# actuator_board.net
KiCad netlist of a schematic drawn in EAGLE
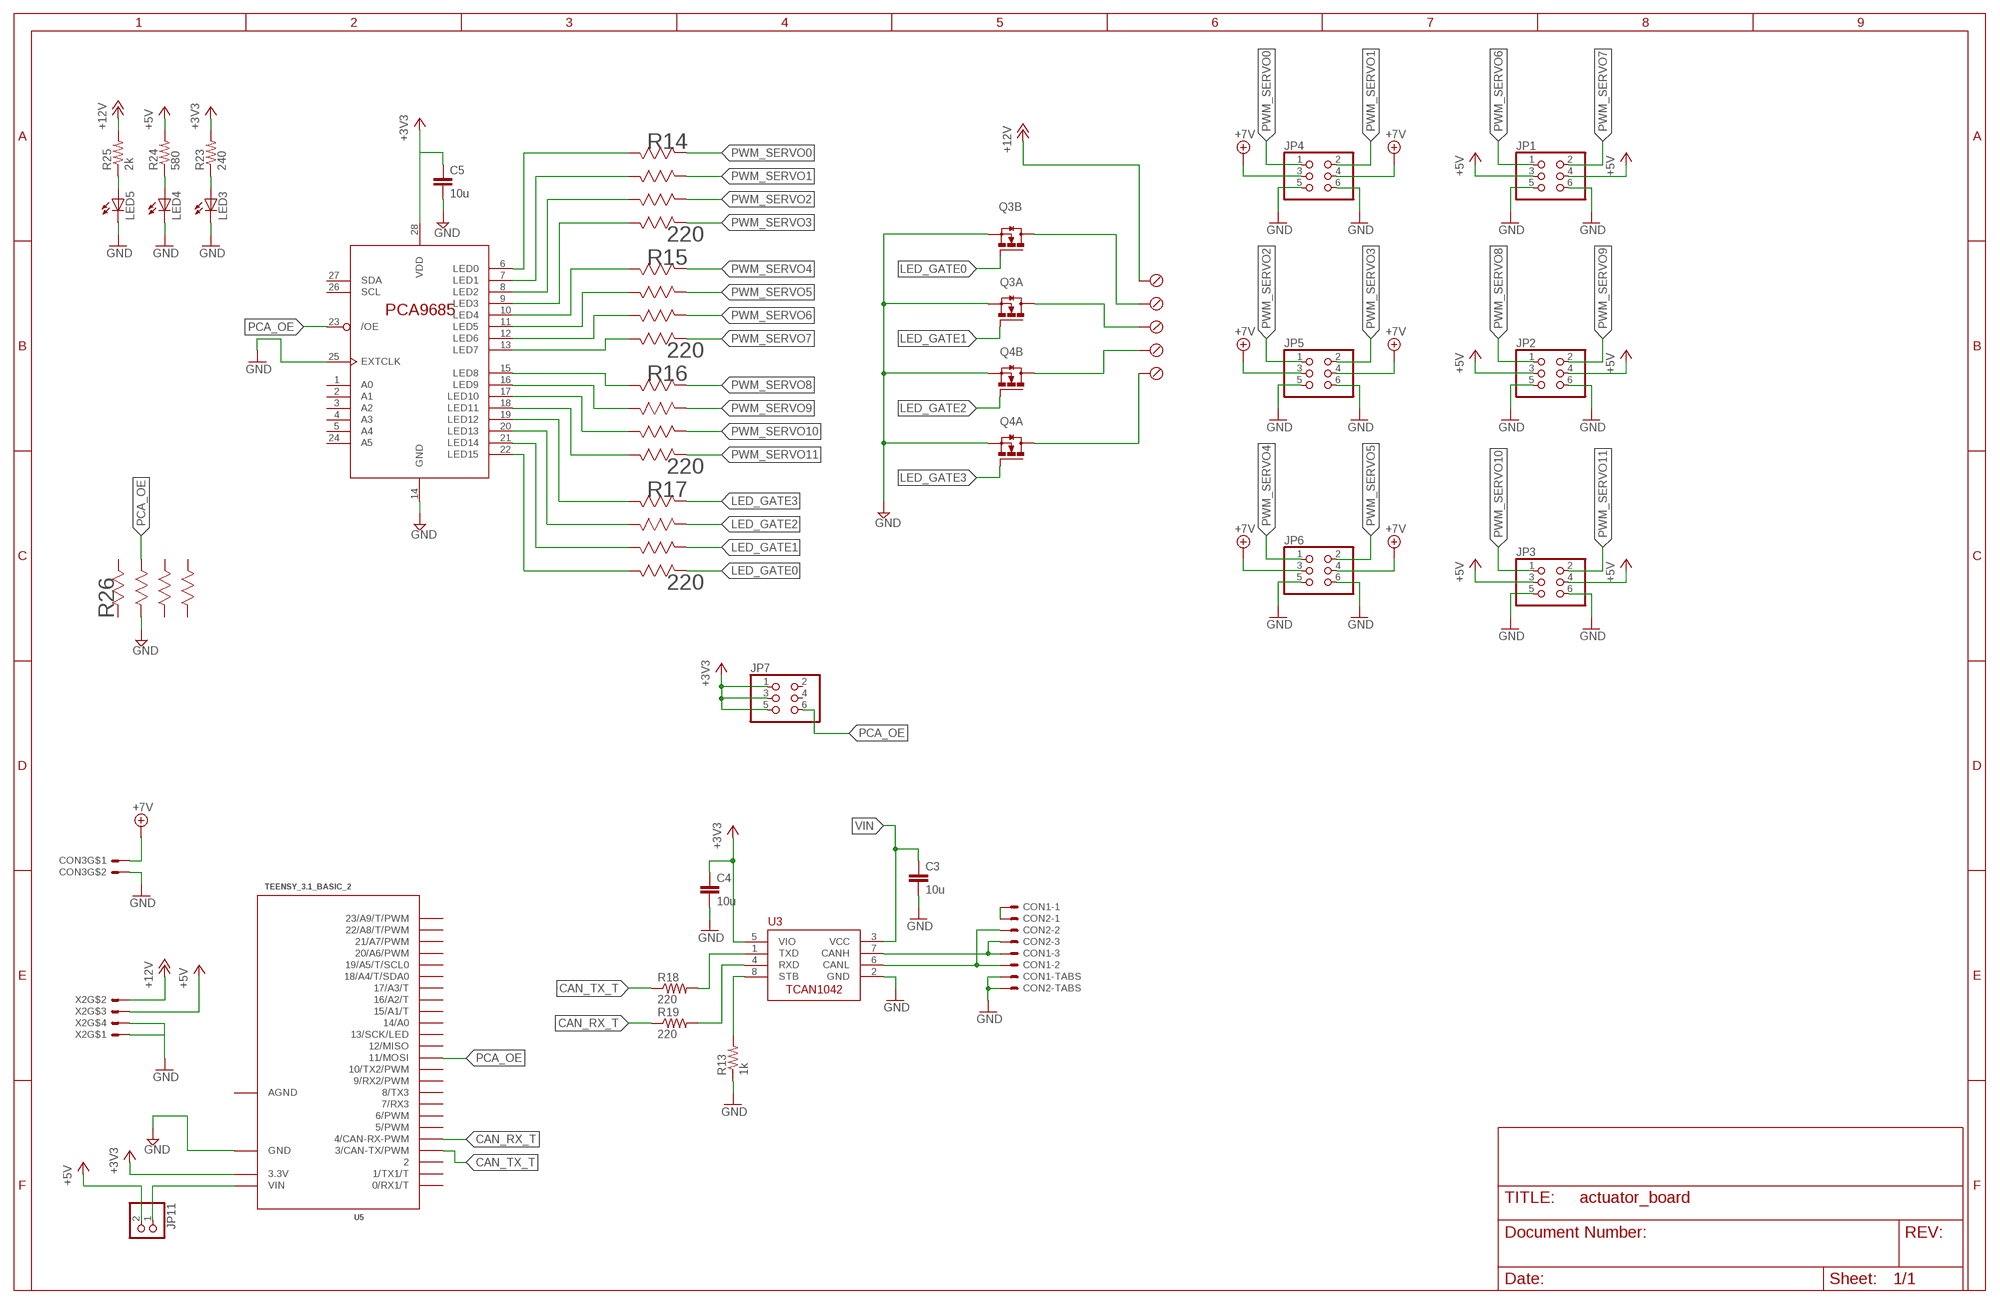
[diagram p0: schematic, sheet 1]

(export (version "E")
  (design (tool "Eeschema 10.0.6"))
  (components
    (comp (ref "C3")
      (value "10u")
      (footprint "eagle-import:C0805")
      (libsource (lib "eagle-import") (part "C-EUC0805"))
    )
    (comp (ref "C4")
      (value "10u")
      (footprint "eagle-import:C0805")
      (libsource (lib "eagle-import") (part "C-EUC0805"))
    )
    (comp (ref "C5")
      (value "10u")
      (footprint "eagle-import:C0805")
      (libsource (lib "eagle-import") (part "C-EUC0805"))
    )
    (comp (ref "CON1")
      (value "SM03B-GHS-TB")
      (footprint "eagle-import:SM03B-GHS-TB")
      (libsource (lib "eagle-import") (part "SM03B-GHS-TB"))
    )
    (comp (ref "CON2")
      (value "SM03B-GHS-TB")
      (footprint "eagle-import:SM03B-GHS-TB")
      (libsource (lib "eagle-import") (part "SM03B-GHS-TB"))
    )
    (comp (ref "CON3")
      (value "MOLEX_5566-2")
      (footprint "eagle-import:5566-2")
      (libsource (lib "eagle-import") (part "MOLEX_5566-2"))
    )
    (comp (ref "JP1")
      (value "PINHD-2X3")
      (footprint "eagle-import:2X03")
      (libsource (lib "eagle-import") (part "PINHD-2X3"))
    )
    (comp (ref "JP2")
      (value "PINHD-2X3")
      (footprint "eagle-import:2X03")
      (libsource (lib "eagle-import") (part "PINHD-2X3"))
    )
    (comp (ref "JP3")
      (value "PINHD-2X3")
      (footprint "eagle-import:2X03")
      (libsource (lib "eagle-import") (part "PINHD-2X3"))
    )
    (comp (ref "JP4")
      (value "PINHD-2X3")
      (footprint "eagle-import:2X03")
      (libsource (lib "eagle-import") (part "PINHD-2X3"))
    )
    (comp (ref "JP5")
      (value "PINHD-2X3")
      (footprint "eagle-import:2X03")
      (libsource (lib "eagle-import") (part "PINHD-2X3"))
    )
    (comp (ref "JP6")
      (value "PINHD-2X3")
      (footprint "eagle-import:2X03")
      (libsource (lib "eagle-import") (part "PINHD-2X3"))
    )
    (comp (ref "JP7")
      (value "PINHD-2X3")
      (footprint "eagle-import:2X03")
      (libsource (lib "eagle-import") (part "PINHD-2X3"))
    )
    (comp (ref "JP11")
      (value "PINHD-1X2")
      (footprint "eagle-import:1X02")
      (libsource (lib "eagle-import") (part "PINHD-1X2"))
    )
    (comp (ref "LED3")
      (value "LEDCHIPLED_1206")
      (footprint "eagle-import:CHIPLED_1206")
      (libsource (lib "eagle-import") (part "LEDCHIPLED_1206"))
    )
    (comp (ref "LED4")
      (value "LEDCHIPLED_1206")
      (footprint "eagle-import:CHIPLED_1206")
      (libsource (lib "eagle-import") (part "LEDCHIPLED_1206"))
    )
    (comp (ref "LED5")
      (value "LEDCHIPLED_1206")
      (footprint "eagle-import:CHIPLED_1206")
      (libsource (lib "eagle-import") (part "LEDCHIPLED_1206"))
    )
    (comp (ref "Q3")
      (value "IRL6372TRPBF")
      (footprint "eagle-import:SO-8")
      (libsource (lib "eagle-import") (part "IRL6372TRPBF"))
    )
    (comp (ref "Q4")
      (value "IRL6372TRPBF")
      (footprint "eagle-import:SO-8")
      (libsource (lib "eagle-import") (part "IRL6372TRPBF"))
    )
    (comp (ref "R13")
      (value "1k")
      (footprint "eagle-import:R0805")
      (libsource (lib "eagle-import") (part "R-US_R0805"))
    )
    (comp (ref "R14")
      (value "220")
      (footprint "eagle-import:EXBV8V-M")
      (fields (field (name "MANUFACTURER_PART_NUMBER") "EXBV8V221JV"))
      (libsource (lib "eagle-import") (part "EXB-V8V221JVEXBV8V-M"))
    )
    (comp (ref "R15")
      (value "220")
      (footprint "eagle-import:EXBV8V-M")
      (fields (field (name "MANUFACTURER_PART_NUMBER") "EXBV8V221JV"))
      (libsource (lib "eagle-import") (part "EXB-V8V221JVEXBV8V-M"))
    )
    (comp (ref "R16")
      (value "220")
      (footprint "eagle-import:EXBV8V-M")
      (fields (field (name "MANUFACTURER_PART_NUMBER") "EXBV8V221JV"))
      (libsource (lib "eagle-import") (part "EXB-V8V221JVEXBV8V-M"))
    )
    (comp (ref "R17")
      (value "220")
      (footprint "eagle-import:EXBV8V-M")
      (fields (field (name "MANUFACTURER_PART_NUMBER") "EXBV8V221JV"))
      (libsource (lib "eagle-import") (part "EXB-V8V221JVEXBV8V-M"))
    )
    (comp (ref "R18")
      (value "220")
      (footprint "eagle-import:R0805")
      (libsource (lib "eagle-import") (part "R-US_R0805"))
    )
    (comp (ref "R19")
      (value "220")
      (footprint "eagle-import:R0805")
      (libsource (lib "eagle-import") (part "R-US_R0805"))
    )
    (comp (ref "R23")
      (value "240")
      (footprint "eagle-import:R1206")
      (libsource (lib "eagle-import") (part "R-US_R1206"))
    )
    (comp (ref "R24")
      (value "580")
      (footprint "eagle-import:R1206")
      (libsource (lib "eagle-import") (part "R-US_R1206"))
    )
    (comp (ref "R25")
      (value "2k")
      (footprint "eagle-import:R1206")
      (libsource (lib "eagle-import") (part "R-US_R1206"))
    )
    (comp (ref "R26")
      (value "10k")
      (footprint "eagle-import:EXBV8V-M")
      (fields (field (name "MANUFACTURER_PART_NUMBER") "EXBV8V221JV"))
      (libsource (lib "eagle-import") (part "EXB-V8V221JVEXBV8V-M"))
    )
    (comp (ref "U$1")
      (value "SCREWLESS_TERMINAL_HEADERSCREWLESS_TERMINAL_HEADER")
      (footprint "eagle-import:1989777_TERMINALHEADER")
      (libsource (lib "eagle-import") (part "SCREWLESS_TERMINAL_HEADERSCREWLESS_TERMINAL_HEADER"))
    )
    (comp (ref "U3")
      (value "TCAN1042HVDR")
      (footprint "eagle-import:SO-8")
      (libsource (lib "eagle-import") (part "TCAN1042HVDR"))
    )
    (comp (ref "U4")
      (value "PCA9685PW")
      (footprint "eagle-import:TSSOP28")
      (libsource (lib "eagle-import") (part "PCA9685PW"))
    )
    (comp (ref "U5")
      (value "TEENSY_3.1_BASIC_2")
      (footprint "eagle-import:TEENSY_3.1_BASIC_2")
      (libsource (lib "eagle-import") (part "TEENSY_3.1_BASIC_2"))
    )
    (comp (ref "X2")
      (value "MOLEX_5566-4")
      (footprint "eagle-import:5566-4")
      (libsource (lib "eagle-import") (part "MOLEX_5566-4"))
    )
  )
  (nets
    (net (code "1") (name "+3V3") (class "Default")
      (node (ref "C4") (pin "1") (pinfunction "1_1") (pintype "passive"))
      (node (ref "C5") (pin "1") (pinfunction "1_1") (pintype "passive"))
      (node (ref "JP7") (pin "1") (pinfunction "1_1") (pintype "passive"))
      (node (ref "JP7") (pin "3") (pinfunction "3_3") (pintype "passive"))
      (node (ref "JP7") (pin "5") (pinfunction "5_5") (pintype "passive"))
      (node (ref "R23") (pin "2") (pinfunction "2_2") (pintype "passive"))
      (node (ref "U3") (pin "5") (pinfunction "VIO_5") (pintype "bidirectional"))
      (node (ref "U4") (pin "28") (pinfunction "VDD_28") (pintype "power_in"))
      (node (ref "U5") (pin "3.3V") (pinfunction "3.3V_3.3V") (pintype "power_in"))
    )
    (net (code "2") (name "+5V") (class "Default")
      (node (ref "JP1") (pin "3") (pinfunction "3_3") (pintype "passive"))
      (node (ref "JP1") (pin "4") (pinfunction "4_4") (pintype "passive"))
      (node (ref "JP11") (pin "2") (pinfunction "2_2") (pintype "passive"))
      (node (ref "JP2") (pin "3") (pinfunction "3_3") (pintype "passive"))
      (node (ref "JP2") (pin "4") (pinfunction "4_4") (pintype "passive"))
      (node (ref "JP3") (pin "3") (pinfunction "3_3") (pintype "passive"))
      (node (ref "JP3") (pin "4") (pinfunction "4_4") (pintype "passive"))
      (node (ref "R24") (pin "2") (pinfunction "2_2") (pintype "passive"))
      (node (ref "X2") (pin "3") (pinfunction "S_3") (pintype "passive"))
    )
    (net (code "3") (name "+7V") (class "Default")
      (node (ref "CON3") (pin "1") (pinfunction "S_1") (pintype "passive"))
      (node (ref "JP4") (pin "3") (pinfunction "3_3") (pintype "passive"))
      (node (ref "JP4") (pin "4") (pinfunction "4_4") (pintype "passive"))
      (node (ref "JP5") (pin "3") (pinfunction "3_3") (pintype "passive"))
      (node (ref "JP5") (pin "4") (pinfunction "4_4") (pintype "passive"))
      (node (ref "JP6") (pin "3") (pinfunction "3_3") (pintype "passive"))
      (node (ref "JP6") (pin "4") (pinfunction "4_4") (pintype "passive"))
    )
    (net (code "4") (name "+12V") (class "Default")
      (node (ref "R25") (pin "2") (pinfunction "2_2") (pintype "passive"))
      (node (ref "U$1") (pin "P$5") (pinfunction "12+_P$5") (pintype "passive"))
      (node (ref "X2") (pin "2") (pinfunction "S_2") (pintype "passive"))
    )
    (net (code "5") (name "/AGND") (class "Default")
      (node (ref "U5") (pin "AGND") (pinfunction "AGND_AGND") (pintype "power_in"))
    )
    (net (code "6") (name "CAN_RX_T") (class "Default")
      (node (ref "R19") (pin "1") (pinfunction "1_1") (pintype "passive"))
      (node (ref "U5") (pin "4") (pinfunction "4/CAN-RX-PWM_4") (pintype "bidirectional"))
    )
    (net (code "7") (name "CAN_TX_T") (class "Default")
      (node (ref "R18") (pin "1") (pinfunction "1_1") (pintype "passive"))
      (node (ref "U5") (pin "3") (pinfunction "3/CAN-TX/PWM_3") (pintype "bidirectional"))
    )
    (net (code "8") (name "GND") (class "Default")
      (node (ref "C3") (pin "2") (pinfunction "2_2") (pintype "passive"))
      (node (ref "C4") (pin "2") (pinfunction "2_2") (pintype "passive"))
      (node (ref "C5") (pin "2") (pinfunction "2_2") (pintype "passive"))
      (node (ref "CON1") (pin "P$4") (pinfunction "S_P$4") (pintype "passive"))
      (node (ref "CON1") (pin "P$5") (pinfunction "S_P$5") (pintype "passive"))
      (node (ref "CON2") (pin "P$4") (pinfunction "S_P$4") (pintype "passive"))
      (node (ref "CON2") (pin "P$5") (pinfunction "S_P$5") (pintype "passive"))
      (node (ref "CON3") (pin "2") (pinfunction "S_2") (pintype "passive"))
      (node (ref "JP1") (pin "5") (pinfunction "5_5") (pintype "passive"))
      (node (ref "JP1") (pin "6") (pinfunction "6_6") (pintype "passive"))
      (node (ref "JP2") (pin "5") (pinfunction "5_5") (pintype "passive"))
      (node (ref "JP2") (pin "6") (pinfunction "6_6") (pintype "passive"))
      (node (ref "JP3") (pin "5") (pinfunction "5_5") (pintype "passive"))
      (node (ref "JP3") (pin "6") (pinfunction "6_6") (pintype "passive"))
      (node (ref "JP4") (pin "5") (pinfunction "5_5") (pintype "passive"))
      (node (ref "JP4") (pin "6") (pinfunction "6_6") (pintype "passive"))
      (node (ref "JP5") (pin "5") (pinfunction "5_5") (pintype "passive"))
      (node (ref "JP5") (pin "6") (pinfunction "6_6") (pintype "passive"))
      (node (ref "JP6") (pin "5") (pinfunction "5_5") (pintype "passive"))
      (node (ref "JP6") (pin "6") (pinfunction "6_6") (pintype "passive"))
      (node (ref "LED3") (pin "C") (pinfunction "C_C") (pintype "passive"))
      (node (ref "LED4") (pin "C") (pinfunction "C_C") (pintype "passive"))
      (node (ref "LED5") (pin "C") (pinfunction "C_C") (pintype "passive"))
      (node (ref "Q3") (pin "1") (pinfunction "S_1") (pintype "passive"))
      (node (ref "Q3") (pin "3") (pinfunction "S_3") (pintype "passive"))
      (node (ref "Q4") (pin "1") (pinfunction "S_1") (pintype "passive"))
      (node (ref "Q4") (pin "3") (pinfunction "S_3") (pintype "passive"))
      (node (ref "R13") (pin "1") (pinfunction "1_1") (pintype "passive"))
      (node (ref "R26") (pin "2") (pinfunction "23_2") (pintype "passive"))
      (node (ref "U3") (pin "2") (pinfunction "GND_2") (pintype "bidirectional"))
      (node (ref "U4") (pin "14") (pinfunction "GND_14") (pintype "power_in"))
      (node (ref "U4") (pin "25") (pinfunction "EXTCLK_25") (pintype "input"))
      (node (ref "U5") (pin "GND") (pinfunction "GND_GND") (pintype "power_in"))
      (node (ref "X2") (pin "1") (pinfunction "S_1") (pintype "passive"))
      (node (ref "X2") (pin "4") (pinfunction "S_4") (pintype "passive"))
    )
    (net (code "9") (name "LED_GATE0") (class "Default")
      (node (ref "Q3") (pin "2") (pinfunction "G_2") (pintype "passive"))
      (node (ref "R17") (pin "4") (pinfunction "47_4") (pintype "passive"))
    )
    (net (code "10") (name "LED_GATE1") (class "Default")
      (node (ref "Q3") (pin "4") (pinfunction "G_4") (pintype "passive"))
      (node (ref "R17") (pin "3") (pinfunction "35_3") (pintype "passive"))
    )
    (net (code "11") (name "LED_GATE2") (class "Default")
      (node (ref "Q4") (pin "2") (pinfunction "G_2") (pintype "passive"))
      (node (ref "R17") (pin "2") (pinfunction "23_2") (pintype "passive"))
    )
    (net (code "12") (name "LED_GATE3") (class "Default")
      (node (ref "Q4") (pin "4") (pinfunction "G_4") (pintype "passive"))
      (node (ref "R17") (pin "1") (pinfunction "11_1") (pintype "passive"))
    )
    (net (code "13") (name "Net-(CON1A-S)") (class "Default")
      (node (ref "CON1") (pin "P$1") (pinfunction "S_P$1") (pintype "passive"))
      (node (ref "CON2") (pin "P$1") (pinfunction "S_P$1") (pintype "passive"))
    )
    (net (code "14") (name "Net-(CON1B-S)") (class "Default")
      (node (ref "CON1") (pin "P$2") (pinfunction "S_P$2") (pintype "passive"))
      (node (ref "CON2") (pin "P$2") (pinfunction "S_P$2") (pintype "passive"))
      (node (ref "U3") (pin "6") (pinfunction "CANL_6") (pintype "bidirectional"))
    )
    (net (code "15") (name "Net-(CON1C-S)") (class "Default")
      (node (ref "CON1") (pin "P$3") (pinfunction "S_P$3") (pintype "passive"))
      (node (ref "CON2") (pin "P$3") (pinfunction "S_P$3") (pintype "passive"))
      (node (ref "U3") (pin "7") (pinfunction "CANH_7") (pintype "bidirectional"))
    )
    (net (code "16") (name "Net-(LED3-PadA)") (class "Default")
      (node (ref "LED3") (pin "A") (pinfunction "A_A") (pintype "passive"))
      (node (ref "R23") (pin "1") (pinfunction "1_1") (pintype "passive"))
    )
    (net (code "17") (name "Net-(LED4-PadA)") (class "Default")
      (node (ref "LED4") (pin "A") (pinfunction "A_A") (pintype "passive"))
      (node (ref "R24") (pin "1") (pinfunction "1_1") (pintype "passive"))
    )
    (net (code "18") (name "Net-(LED5-PadA)") (class "Default")
      (node (ref "LED5") (pin "A") (pinfunction "A_A") (pintype "passive"))
      (node (ref "R25") (pin "1") (pinfunction "1_1") (pintype "passive"))
    )
    (net (code "19") (name "Net-(R14-58)") (class "Default")
      (node (ref "R14") (pin "5") (pinfunction "58_5") (pintype "passive"))
      (node (ref "U4") (pin "9") (pinfunction "LED3_9") (pintype "bidirectional"))
    )
    (net (code "20") (name "Net-(R14-66)") (class "Default")
      (node (ref "R14") (pin "6") (pinfunction "66_6") (pintype "passive"))
      (node (ref "U4") (pin "8") (pinfunction "LED2_8") (pintype "bidirectional"))
    )
    (net (code "21") (name "Net-(R14-74)") (class "Default")
      (node (ref "R14") (pin "7") (pinfunction "74_7") (pintype "passive"))
      (node (ref "U4") (pin "7") (pinfunction "LED1_7") (pintype "bidirectional"))
    )
    (net (code "22") (name "Net-(R14-82)") (class "Default")
      (node (ref "R14") (pin "8") (pinfunction "82_8") (pintype "passive"))
      (node (ref "U4") (pin "6") (pinfunction "LED0_6") (pintype "bidirectional"))
    )
    (net (code "23") (name "Net-(R15-58)") (class "Default")
      (node (ref "R15") (pin "5") (pinfunction "58_5") (pintype "passive"))
      (node (ref "U4") (pin "13") (pinfunction "LED7_13") (pintype "bidirectional"))
    )
    (net (code "24") (name "Net-(R15-66)") (class "Default")
      (node (ref "R15") (pin "6") (pinfunction "66_6") (pintype "passive"))
      (node (ref "U4") (pin "12") (pinfunction "LED6_12") (pintype "bidirectional"))
    )
    (net (code "25") (name "Net-(R15-74)") (class "Default")
      (node (ref "R15") (pin "7") (pinfunction "74_7") (pintype "passive"))
      (node (ref "U4") (pin "11") (pinfunction "LED5_11") (pintype "bidirectional"))
    )
    (net (code "26") (name "Net-(R15-82)") (class "Default")
      (node (ref "R15") (pin "8") (pinfunction "82_8") (pintype "passive"))
      (node (ref "U4") (pin "10") (pinfunction "LED4_10") (pintype "bidirectional"))
    )
    (net (code "27") (name "Net-(R16-58)") (class "Default")
      (node (ref "R16") (pin "5") (pinfunction "58_5") (pintype "passive"))
      (node (ref "U4") (pin "18") (pinfunction "LED11_18") (pintype "bidirectional"))
    )
    (net (code "28") (name "Net-(R16-66)") (class "Default")
      (node (ref "R16") (pin "6") (pinfunction "66_6") (pintype "passive"))
      (node (ref "U4") (pin "17") (pinfunction "LED10_17") (pintype "bidirectional"))
    )
    (net (code "29") (name "Net-(R16-74)") (class "Default")
      (node (ref "R16") (pin "7") (pinfunction "74_7") (pintype "passive"))
      (node (ref "U4") (pin "16") (pinfunction "LED9_16") (pintype "bidirectional"))
    )
    (net (code "30") (name "Net-(R16-82)") (class "Default")
      (node (ref "R16") (pin "8") (pinfunction "82_8") (pintype "passive"))
      (node (ref "U4") (pin "15") (pinfunction "LED8_15") (pintype "bidirectional"))
    )
    (net (code "31") (name "Net-(R17-58)") (class "Default")
      (node (ref "R17") (pin "5") (pinfunction "58_5") (pintype "passive"))
      (node (ref "U4") (pin "22") (pinfunction "LED15_22") (pintype "bidirectional"))
    )
    (net (code "32") (name "Net-(R17-66)") (class "Default")
      (node (ref "R17") (pin "6") (pinfunction "66_6") (pintype "passive"))
      (node (ref "U4") (pin "21") (pinfunction "LED14_21") (pintype "bidirectional"))
    )
    (net (code "33") (name "Net-(R17-74)") (class "Default")
      (node (ref "R17") (pin "7") (pinfunction "74_7") (pintype "passive"))
      (node (ref "U4") (pin "20") (pinfunction "LED13_20") (pintype "bidirectional"))
    )
    (net (code "34") (name "Net-(R17-82)") (class "Default")
      (node (ref "R17") (pin "8") (pinfunction "82_8") (pintype "passive"))
      (node (ref "U4") (pin "19") (pinfunction "LED12_19") (pintype "bidirectional"))
    )
    (net (code "35") (name "Net-(U$1-LED0)") (class "Default")
      (node (ref "Q3") (pin "7") (pinfunction "D_7") (pintype "passive"))
      (node (ref "Q3") (pin "8") (pinfunction "D_8") (pintype "passive"))
      (node (ref "U$1") (pin "P$4") (pinfunction "LED0_P$4") (pintype "passive"))
    )
    (net (code "36") (name "Net-(U$1-LED1)") (class "Default")
      (node (ref "Q3") (pin "5") (pinfunction "D_5") (pintype "passive"))
      (node (ref "Q3") (pin "6") (pinfunction "D_6") (pintype "passive"))
      (node (ref "U$1") (pin "P$3") (pinfunction "LED1_P$3") (pintype "passive"))
    )
    (net (code "37") (name "Net-(U$1-LED2)") (class "Default")
      (node (ref "Q4") (pin "7") (pinfunction "D_7") (pintype "passive"))
      (node (ref "Q4") (pin "8") (pinfunction "D_8") (pintype "passive"))
      (node (ref "U$1") (pin "P$2") (pinfunction "LED2_P$2") (pintype "passive"))
    )
    (net (code "38") (name "Net-(U$1-LED3)") (class "Default")
      (node (ref "Q4") (pin "5") (pinfunction "D_5") (pintype "passive"))
      (node (ref "Q4") (pin "6") (pinfunction "D_6") (pintype "passive"))
      (node (ref "U$1") (pin "P$1") (pinfunction "LED3_P$1") (pintype "passive"))
    )
    (net (code "39") (name "Net-(U3-RXD)") (class "Default")
      (node (ref "R19") (pin "2") (pinfunction "2_2") (pintype "passive"))
      (node (ref "U3") (pin "4") (pinfunction "RXD_4") (pintype "bidirectional"))
    )
    (net (code "40") (name "Net-(U3-STB)") (class "Default")
      (node (ref "R13") (pin "2") (pinfunction "2_2") (pintype "passive"))
      (node (ref "U3") (pin "8") (pinfunction "STB_8") (pintype "bidirectional"))
    )
    (net (code "41") (name "Net-(U3-TXD)") (class "Default")
      (node (ref "R18") (pin "2") (pinfunction "2_2") (pintype "passive"))
      (node (ref "U3") (pin "1") (pinfunction "TXD_1") (pintype "bidirectional"))
    )
    (net (code "42") (name "PCA_OE") (class "Default")
      (node (ref "JP7") (pin "6") (pinfunction "6_6") (pintype "passive"))
      (node (ref "R26") (pin "7") (pinfunction "74_7") (pintype "passive"))
      (node (ref "U4") (pin "23") (pinfunction "/OE_23") (pintype "bidirectional"))
      (node (ref "U5") (pin "11") (pinfunction "11/MOSI_11") (pintype "bidirectional"))
    )
    (net (code "43") (name "PWM_SERVO0") (class "Default")
      (node (ref "JP4") (pin "1") (pinfunction "1_1") (pintype "passive"))
      (node (ref "R14") (pin "1") (pinfunction "11_1") (pintype "passive"))
    )
    (net (code "44") (name "PWM_SERVO1") (class "Default")
      (node (ref "JP4") (pin "2") (pinfunction "2_2") (pintype "passive"))
      (node (ref "R14") (pin "2") (pinfunction "23_2") (pintype "passive"))
    )
    (net (code "45") (name "PWM_SERVO2") (class "Default")
      (node (ref "JP5") (pin "1") (pinfunction "1_1") (pintype "passive"))
      (node (ref "R14") (pin "3") (pinfunction "35_3") (pintype "passive"))
    )
    (net (code "46") (name "PWM_SERVO3") (class "Default")
      (node (ref "JP5") (pin "2") (pinfunction "2_2") (pintype "passive"))
      (node (ref "R14") (pin "4") (pinfunction "47_4") (pintype "passive"))
    )
    (net (code "47") (name "PWM_SERVO4") (class "Default")
      (node (ref "JP6") (pin "1") (pinfunction "1_1") (pintype "passive"))
      (node (ref "R15") (pin "1") (pinfunction "11_1") (pintype "passive"))
    )
    (net (code "48") (name "PWM_SERVO5") (class "Default")
      (node (ref "JP6") (pin "2") (pinfunction "2_2") (pintype "passive"))
      (node (ref "R15") (pin "2") (pinfunction "23_2") (pintype "passive"))
    )
    (net (code "49") (name "PWM_SERVO6") (class "Default")
      (node (ref "JP1") (pin "1") (pinfunction "1_1") (pintype "passive"))
      (node (ref "R15") (pin "3") (pinfunction "35_3") (pintype "passive"))
    )
    (net (code "50") (name "PWM_SERVO7") (class "Default")
      (node (ref "JP1") (pin "2") (pinfunction "2_2") (pintype "passive"))
      (node (ref "R15") (pin "4") (pinfunction "47_4") (pintype "passive"))
    )
    (net (code "51") (name "PWM_SERVO8") (class "Default")
      (node (ref "JP2") (pin "1") (pinfunction "1_1") (pintype "passive"))
      (node (ref "R16") (pin "1") (pinfunction "11_1") (pintype "passive"))
    )
    (net (code "52") (name "PWM_SERVO9") (class "Default")
      (node (ref "JP2") (pin "2") (pinfunction "2_2") (pintype "passive"))
      (node (ref "R16") (pin "2") (pinfunction "23_2") (pintype "passive"))
    )
    (net (code "53") (name "PWM_SERVO10") (class "Default")
      (node (ref "JP3") (pin "1") (pinfunction "1_1") (pintype "passive"))
      (node (ref "R16") (pin "3") (pinfunction "35_3") (pintype "passive"))
    )
    (net (code "54") (name "PWM_SERVO11") (class "Default")
      (node (ref "JP3") (pin "2") (pinfunction "2_2") (pintype "passive"))
      (node (ref "R16") (pin "4") (pinfunction "47_4") (pintype "passive"))
    )
    (net (code "55") (name "VIN") (class "Default")
      (node (ref "C3") (pin "1") (pinfunction "1_1") (pintype "passive"))
      (node (ref "JP11") (pin "1") (pinfunction "1_1") (pintype "passive"))
      (node (ref "U3") (pin "3") (pinfunction "VCC_3") (pintype "bidirectional"))
      (node (ref "U5") (pin "VIN") (pinfunction "VIN_VIN") (pintype "power_in"))
    )
    (net (code "56") (name "unconnected-(JP7-Pad2)") (class "Default")
      (node (ref "JP7") (pin "2") (pinfunction "2_2") (pintype "passive"))
    )
    (net (code "57") (name "unconnected-(JP7-Pad4)") (class "Default")
      (node (ref "JP7") (pin "4") (pinfunction "4_4") (pintype "passive"))
    )
    (net (code "58") (name "unconnected-(R26-11-Pad1)") (class "Default")
      (node (ref "R26") (pin "1") (pinfunction "11_1") (pintype "passive"))
    )
    (net (code "59") (name "unconnected-(R26-35-Pad3)") (class "Default")
      (node (ref "R26") (pin "3") (pinfunction "35_3") (pintype "passive"))
    )
    (net (code "60") (name "unconnected-(R26-47-Pad4)") (class "Default")
      (node (ref "R26") (pin "4") (pinfunction "47_4") (pintype "passive"))
    )
    (net (code "61") (name "unconnected-(R26-58-Pad5)") (class "Default")
      (node (ref "R26") (pin "5") (pinfunction "58_5") (pintype "passive"))
    )
    (net (code "62") (name "unconnected-(R26-66-Pad6)") (class "Default")
      (node (ref "R26") (pin "6") (pinfunction "66_6") (pintype "passive"))
    )
    (net (code "63") (name "unconnected-(R26-82-Pad8)") (class "Default")
      (node (ref "R26") (pin "8") (pinfunction "82_8") (pintype "passive"))
    )
    (net (code "64") (name "unconnected-(U4-A0-Pad1)") (class "Default")
      (node (ref "U4") (pin "1") (pinfunction "A0_1") (pintype "bidirectional"))
    )
    (net (code "65") (name "unconnected-(U4-A1-Pad2)") (class "Default")
      (node (ref "U4") (pin "2") (pinfunction "A1_2") (pintype "bidirectional"))
    )
    (net (code "66") (name "unconnected-(U4-A2-Pad3)") (class "Default")
      (node (ref "U4") (pin "3") (pinfunction "A2_3") (pintype "bidirectional"))
    )
    (net (code "67") (name "unconnected-(U4-A3-Pad4)") (class "Default")
      (node (ref "U4") (pin "4") (pinfunction "A3_4") (pintype "bidirectional"))
    )
    (net (code "68") (name "unconnected-(U4-A4-Pad5)") (class "Default")
      (node (ref "U4") (pin "5") (pinfunction "A4_5") (pintype "bidirectional"))
    )
    (net (code "69") (name "unconnected-(U4-A5-Pad24)") (class "Default")
      (node (ref "U4") (pin "24") (pinfunction "A5_24") (pintype "bidirectional"))
    )
    (net (code "70") (name "unconnected-(U4-SCL-Pad26)") (class "Default")
      (node (ref "U4") (pin "26") (pinfunction "SCL_26") (pintype "bidirectional"))
    )
    (net (code "71") (name "unconnected-(U4-SDA-Pad27)") (class "Default")
      (node (ref "U4") (pin "27") (pinfunction "SDA_27") (pintype "bidirectional"))
    )
    (net (code "72") (name "unconnected-(U5-0{slash}RX1{slash}T-Pad0)") (class "Default")
      (node (ref "U5") (pin "0") (pinfunction "0/RX1/T_0") (pintype "bidirectional"))
    )
    (net (code "73") (name "unconnected-(U5-1{slash}TX1{slash}T-Pad1)") (class "Default")
      (node (ref "U5") (pin "1") (pinfunction "1/TX1/T_1") (pintype "bidirectional"))
    )
    (net (code "74") (name "unconnected-(U5-5{slash}PWM-Pad5)") (class "Default")
      (node (ref "U5") (pin "5") (pinfunction "5/PWM_5") (pintype "bidirectional"))
    )
    (net (code "75") (name "unconnected-(U5-6{slash}PWM-Pad6)") (class "Default")
      (node (ref "U5") (pin "6") (pinfunction "6/PWM_6") (pintype "bidirectional"))
    )
    (net (code "76") (name "unconnected-(U5-7{slash}RX3-Pad7)") (class "Default")
      (node (ref "U5") (pin "7") (pinfunction "7/RX3_7") (pintype "bidirectional"))
    )
    (net (code "77") (name "unconnected-(U5-8{slash}TX3-Pad8)") (class "Default")
      (node (ref "U5") (pin "8") (pinfunction "8/TX3_8") (pintype "bidirectional"))
    )
    (net (code "78") (name "unconnected-(U5-9{slash}RX2{slash}PWM-Pad9)") (class "Default")
      (node (ref "U5") (pin "9") (pinfunction "9/RX2/PWM_9") (pintype "bidirectional"))
    )
    (net (code "79") (name "unconnected-(U5-10{slash}TX2{slash}PWM-Pad10)") (class "Default")
      (node (ref "U5") (pin "10") (pinfunction "10/TX2/PWM_10") (pintype "bidirectional"))
    )
    (net (code "80") (name "unconnected-(U5-12{slash}MISO-Pad12)") (class "Default")
      (node (ref "U5") (pin "12") (pinfunction "12/MISO_12") (pintype "bidirectional"))
    )
    (net (code "81") (name "unconnected-(U5-13{slash}SCK{slash}LED-Pad13)") (class "Default")
      (node (ref "U5") (pin "13") (pinfunction "13/SCK/LED_13") (pintype "bidirectional"))
    )
    (net (code "82") (name "unconnected-(U5-15{slash}A1{slash}T-Pad15{slash}A1)") (class "Default")
      (node (ref "U5") (pin "15/A1") (pinfunction "15/A1/T_15/A1") (pintype "bidirectional"))
    )
    (net (code "83") (name "unconnected-(U5-16{slash}A2{slash}T-Pad16{slash}A2)") (class "Default")
      (node (ref "U5") (pin "16/A2") (pinfunction "16/A2/T_16/A2") (pintype "bidirectional"))
    )
    (net (code "84") (name "unconnected-(U5-17{slash}A3{slash}T-Pad17{slash}A3)") (class "Default")
      (node (ref "U5") (pin "17/A3") (pinfunction "17/A3/T_17/A3") (pintype "bidirectional"))
    )
    (net (code "85") (name "unconnected-(U5-18{slash}A4{slash}T{slash}SDA0-Pad18{slash}A4)") (class "Default")
      (node (ref "U5") (pin "18/A4") (pinfunction "18/A4/T/SDA0_18/A4") (pintype "bidirectional"))
    )
    (net (code "86") (name "unconnected-(U5-19{slash}A5{slash}T{slash}SCL0-Pad19{slash}A5)") (class "Default")
      (node (ref "U5") (pin "19/A5") (pinfunction "19/A5/T/SCL0_19/A5") (pintype "bidirectional"))
    )
    (net (code "87") (name "unconnected-(U5-20{slash}A6{slash}PWM-Pad20{slash}A6)") (class "Default")
      (node (ref "U5") (pin "20/A6") (pinfunction "20/A6/PWM_20/A6") (pintype "bidirectional"))
    )
    (net (code "88") (name "unconnected-(U5-21{slash}A7{slash}PWM-Pad21{slash}A7)") (class "Default")
      (node (ref "U5") (pin "21/A7") (pinfunction "21/A7/PWM_21/A7") (pintype "bidirectional"))
    )
    (net (code "89") (name "unconnected-(U5-22{slash}A8{slash}T{slash}PWM-Pad22{slash}A8)") (class "Default")
      (node (ref "U5") (pin "22/A8") (pinfunction "22/A8/T/PWM_22/A8") (pintype "bidirectional"))
    )
    (net (code "90") (name "unconnected-(U5-23{slash}A9{slash}T{slash}PWM-Pad23{slash}A9)") (class "Default")
      (node (ref "U5") (pin "23/A9") (pinfunction "23/A9/T/PWM_23/A9") (pintype "bidirectional"))
    )
    (net (code "91") (name "unconnected-(U5-Pad2)") (class "Default")
      (node (ref "U5") (pin "2") (pinfunction "2_2") (pintype "bidirectional"))
    )
    (net (code "92") (name "unconnected-(U5-Pad14{slash}A0)") (class "Default")
      (node (ref "U5") (pin "14/A0") (pinfunction "14/A0_14/A0") (pintype "bidirectional"))
    )
  )
)
